# MPU9250.net
KiCad netlist of a schematic drawn in Altium Designer
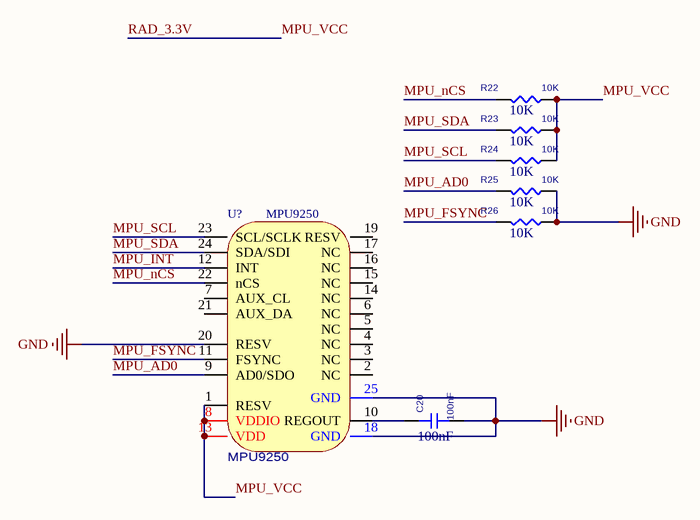
[diagram p0: MPU9250.SchDoc]

(export (version "E")
  (design (tool "Eeschema 10.0.6"))
  (components
    (comp (ref "C20")
      (value "100nF")
      (footprint "C0603")
      (fields (field (name "VOLTAGE") "CMAX") (field (name "ALTIUM_VALUE") "100nF"))
      (libsource (lib "*") (part "CAP1"))
    )
    (comp (ref "R22")
      (value "10K")
      (footprint "R0603")
      (fields
        (field (name "VOLTAGE") "RVMAX")
        (field (name "POWER") "RMAX")
        (field (name "ALTIUM_VALUE") "10K")
      )
      (libsource (lib "*") (part "RES1"))
    )
    (comp (ref "R23")
      (value "10K")
      (footprint "R0603")
      (fields
        (field (name "VOLTAGE") "RVMAX")
        (field (name "POWER") "RMAX")
        (field (name "ALTIUM_VALUE") "10K")
      )
      (libsource (lib "*") (part "RES1"))
    )
    (comp (ref "R24")
      (value "10K")
      (footprint "R0603")
      (fields
        (field (name "VOLTAGE") "RVMAX")
        (field (name "POWER") "RMAX")
        (field (name "ALTIUM_VALUE") "10K")
      )
      (libsource (lib "*") (part "RES1"))
    )
    (comp (ref "R25")
      (value "10K")
      (footprint "R0603")
      (fields
        (field (name "VOLTAGE") "RVMAX")
        (field (name "POWER") "RMAX")
        (field (name "ALTIUM_VALUE") "10K")
      )
      (libsource (lib "*") (part "RES1"))
    )
    (comp (ref "R26")
      (value "10K")
      (footprint "R0603")
      (fields
        (field (name "VOLTAGE") "RVMAX")
        (field (name "POWER") "RMAX")
        (field (name "ALTIUM_VALUE") "10K")
      )
      (libsource (lib "*") (part "RES1"))
    )
    (comp (ref "U7") (value "MPU9250") (footprint "MPU9250") (libsource (lib "MZ7XB_Fun") (part "MPU9250")))
  )
  (nets
    (net (code "1") (name "/MPU_AD0") (class "Default")
      (node (ref "R25") (pin "1") (pinfunction "1_1") (pintype "passive"))
      (node (ref "U7") (pin "9") (pinfunction "AD0/SDO_9") (pintype "passive"))
    )
    (net (code "2") (name "/MPU_FSYNC") (class "Default")
      (node (ref "R26") (pin "1") (pinfunction "1_1") (pintype "passive"))
      (node (ref "U7") (pin "11") (pinfunction "FSYNC_11") (pintype "passive"))
    )
    (net (code "3") (name "/MPU_INT") (class "Default")
      (node (ref "U7") (pin "12") (pinfunction "INT_12") (pintype "passive"))
    )
    (net (code "4") (name "/MPU_SCL") (class "Default")
      (node (ref "R24") (pin "1") (pinfunction "1_1") (pintype "passive"))
      (node (ref "U7") (pin "23") (pinfunction "SCL/SCLK_23") (pintype "passive"))
    )
    (net (code "5") (name "/MPU_SDA") (class "Default")
      (node (ref "R23") (pin "1") (pinfunction "1_1") (pintype "passive"))
      (node (ref "U7") (pin "24") (pinfunction "SDA/SDI_24") (pintype "passive"))
    )
    (net (code "6") (name "/MPU_VCC") (class "Default")
      (node (ref "R22") (pin "2") (pinfunction "2_2") (pintype "passive"))
      (node (ref "R23") (pin "2") (pinfunction "2_2") (pintype "passive"))
      (node (ref "R24") (pin "2") (pinfunction "2_2") (pintype "passive"))
      (node (ref "U7") (pin "1") (pinfunction "RESV_1") (pintype "passive"))
      (node (ref "U7") (pin "13") (pinfunction "VDD_13") (pintype "passive"))
      (node (ref "U7") (pin "8") (pinfunction "VDDIO_8") (pintype "passive"))
    )
    (net (code "7") (name "/MPU_nCS") (class "Default")
      (node (ref "R22") (pin "1") (pinfunction "1_1") (pintype "passive"))
      (node (ref "U7") (pin "22") (pinfunction "nCS_22") (pintype "passive"))
    )
    (net (code "8") (name "GND") (class "Default")
      (node (ref "C20") (pin "1") (pinfunction "1_1") (pintype "passive"))
      (node (ref "R25") (pin "2") (pinfunction "2_2") (pintype "passive"))
      (node (ref "R26") (pin "2") (pinfunction "2_2") (pintype "passive"))
      (node (ref "U7") (pin "18") (pinfunction "GND_18") (pintype "passive"))
      (node (ref "U7") (pin "20") (pinfunction "RESV_20") (pintype "passive"))
      (node (ref "U7") (pin "25") (pinfunction "GND_25") (pintype "passive"))
    )
    (net (code "9") (name "Net-(U7-REGOUT)") (class "Default")
      (node (ref "C20") (pin "2") (pinfunction "2_2") (pintype "passive"))
      (node (ref "U7") (pin "10") (pinfunction "REGOUT_10") (pintype "passive"))
    )
    (net (code "10") (name "unconnected-(U7-AUX_CL-Pad7)") (class "Default")
      (node (ref "U7") (pin "7") (pinfunction "AUX_CL_7") (pintype "passive"))
    )
    (net (code "11") (name "unconnected-(U7-AUX_DA-Pad21)") (class "Default")
      (node (ref "U7") (pin "21") (pinfunction "AUX_DA_21") (pintype "passive"))
    )
    (net (code "12") (name "unconnected-(U7-NC-Pad2)") (class "Default")
      (node (ref "U7") (pin "2") (pinfunction "NC_2") (pintype "passive"))
    )
    (net (code "13") (name "unconnected-(U7-NC-Pad3)") (class "Default")
      (node (ref "U7") (pin "3") (pinfunction "NC_3") (pintype "passive"))
    )
    (net (code "14") (name "unconnected-(U7-NC-Pad4)") (class "Default")
      (node (ref "U7") (pin "4") (pinfunction "NC_4") (pintype "passive"))
    )
    (net (code "15") (name "unconnected-(U7-NC-Pad5)") (class "Default")
      (node (ref "U7") (pin "5") (pinfunction "NC_5") (pintype "passive"))
    )
    (net (code "16") (name "unconnected-(U7-NC-Pad6)") (class "Default")
      (node (ref "U7") (pin "6") (pinfunction "NC_6") (pintype "passive"))
    )
    (net (code "17") (name "unconnected-(U7-NC-Pad14)") (class "Default")
      (node (ref "U7") (pin "14") (pinfunction "NC_14") (pintype "passive"))
    )
    (net (code "18") (name "unconnected-(U7-NC-Pad15)") (class "Default")
      (node (ref "U7") (pin "15") (pinfunction "NC_15") (pintype "passive"))
    )
    (net (code "19") (name "unconnected-(U7-NC-Pad16)") (class "Default")
      (node (ref "U7") (pin "16") (pinfunction "NC_16") (pintype "passive"))
    )
    (net (code "20") (name "unconnected-(U7-NC-Pad17)") (class "Default")
      (node (ref "U7") (pin "17") (pinfunction "NC_17") (pintype "passive"))
    )
    (net (code "21") (name "unconnected-(U7-RESV-Pad19)") (class "Default")
      (node (ref "U7") (pin "19") (pinfunction "RESV_19") (pintype "passive"))
    )
  )
)
